# POWER.net
KiCad netlist of a schematic drawn in Altium Designer
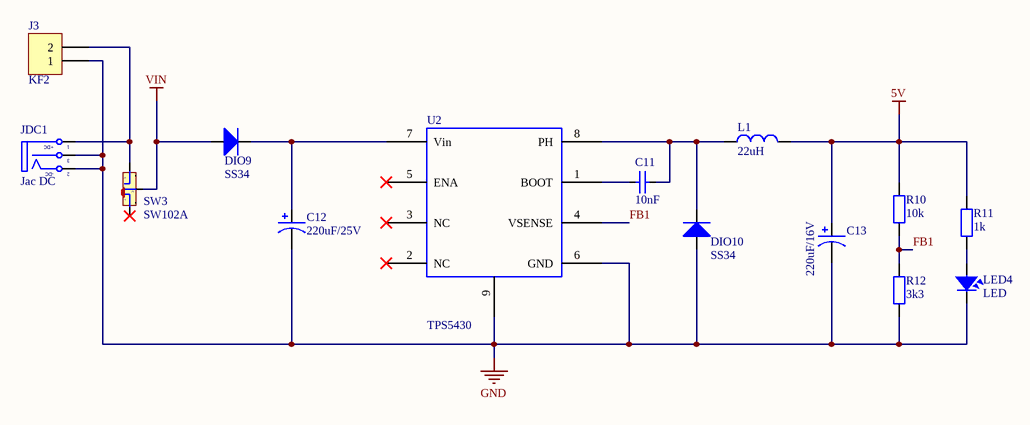
[diagram p0: POWER.SchDoc]

(export (version "E")
  (design (tool "Eeschema 10.0.6"))
  (components
    (comp (ref "C11")
      (value "10nF")
      (footprint "CAP_0805")
      (description "Capacitor")
      (fields (field (name "PUBLISHER") "Altium Limited"))
      (libsource (lib "My Library") (part "CapSMD"))
    )
    (comp (ref "C12")
      (value "220uF/25V")
      (footprint "C8mm")
      (description "Polarized Capacitor (Axial)")
      (fields (field (name "PUBLISHER") "Altium Limited"))
      (libsource (lib "My Library") (part "Cap Pol"))
    )
    (comp (ref "C13")
      (value "220uF/16V")
      (footprint "C8mm")
      (description "Polarized Capacitor (Axial)")
      (fields (field (name "PUBLISHER") "Altium Limited"))
      (libsource (lib "My Library") (part "Cap Pol"))
    )
    (comp (ref "DIO9")
      (value "SS34")
      (footprint "DIO-214AC(SMA)")
      (description "Default Diode")
      (fields (field (name "PUBLISHER") "Altium Limited"))
      (libsource (lib "My Library") (part "Diode SMD"))
    )
    (comp (ref "DIO10")
      (value "SS34")
      (footprint "DIO-214AC(SMA)")
      (description "Default Diode")
      (fields (field (name "PUBLISHER") "Altium Limited"))
      (libsource (lib "My Library") (part "Diode SMD"))
    )
    (comp (ref "J3")
      (value "KF2")
      (footprint "KF2-5.08")
      (fields
        (field (name "MANUFACTURER") "Würth Elektronik eiSos GmbH")
        (field (name "PARTNO") "691103110002")
        (field (name "CREATED BY") "Karrer Zheng")
      )
      (libsource (lib "My Library") (part "KF2"))
    )
    (comp (ref "JDC1")
      (value "Jac DC")
      (footprint "DC-IN")
      (description "Jac DC input")
      (libsource (lib "My Library") (part "DCIN"))
    )
    (comp (ref "L1")
      (value "22uH")
      (footprint "L-SMD-M-7.3x4.5")
      (description "Inductor")
      (libsource (lib "My Library") (part "Inductor"))
    )
    (comp (ref "LED4")
      (value "LED")
      (footprint "LED-0805-Red")
      (description "LED Single colour Green and Red")
      (libsource (lib "My Library") (part "LED"))
    )
    (comp (ref "R10")
      (value "10k")
      (footprint "RES-SMD-0805")
      (description "Resistor SMD")
      (fields
        (field (name "MANUFACTURER") "Generic Components")
        (field (name "PUBLISHER") "Altium Hobart Technology Centre")
      )
      (libsource (lib "My Library") (part "Resistor - SMD"))
    )
    (comp (ref "R11")
      (value "1k")
      (footprint "RES-SMD-0805")
      (description "Resistor SMD")
      (fields
        (field (name "MANUFACTURER") "Generic Components")
        (field (name "PUBLISHER") "Altium Hobart Technology Centre")
      )
      (libsource (lib "My Library") (part "Resistor - SMD"))
    )
    (comp (ref "R12")
      (value "3k3")
      (footprint "RES-SMD-0805")
      (description "Resistor SMD")
      (fields
        (field (name "MANUFACTURER") "Generic Components")
        (field (name "PUBLISHER") "Altium Hobart Technology Centre")
      )
      (libsource (lib "My Library") (part "Resistor - SMD"))
    )
    (comp (ref "SW3")
      (value "SW102A")
      (footprint "SW102")
      (description "Switch 102 on Broad")
      (libsource (lib "My Library") (part "SW102A"))
    )
    (comp (ref "U2")
      (value "TPS5430")
      (footprint "ESOP-8")
      (fields (field (name "NAME") "TPS5430"))
      (libsource (lib "My Library") (part "TPS5430"))
    )
  )
  (nets
    (net (code "1") (name "/FB1") (class "Default")
      (node (ref "R10") (pin "2") (pinfunction "2_2") (pintype "passive"))
      (node (ref "R12") (pin "1") (pinfunction "1_1") (pintype "passive"))
      (node (ref "U2") (pin "4") (pinfunction "VSENSE_4") (pintype "passive"))
    )
    (net (code "2") (name "5V") (class "Default")
      (node (ref "C13") (pin "1") (pinfunction "1_1") (pintype "passive"))
      (node (ref "L1") (pin "2") (pinfunction "2_2") (pintype "passive"))
      (node (ref "R10") (pin "1") (pinfunction "1_1") (pintype "passive"))
      (node (ref "R11") (pin "1") (pinfunction "1_1") (pintype "passive"))
    )
    (net (code "3") (name "GND") (class "Default")
      (node (ref "C12") (pin "2") (pinfunction "2_2") (pintype "passive"))
      (node (ref "C13") (pin "2") (pinfunction "2_2") (pintype "passive"))
      (node (ref "DIO10") (pin "1") (pinfunction "A_1") (pintype "passive"))
      (node (ref "J3") (pin "1") (pinfunction "1_1") (pintype "passive"))
      (node (ref "JDC1") (pin "2") (pinfunction "TN_2") (pintype "passive"))
      (node (ref "JDC1") (pin "3") (pinfunction "S_3") (pintype "power_in"))
      (node (ref "LED4") (pin "2") (pinfunction "2_2") (pintype "passive"))
      (node (ref "R12") (pin "2") (pinfunction "2_2") (pintype "passive"))
      (node (ref "U2") (pin "6") (pinfunction "GND_6") (pintype "passive"))
      (node (ref "U2") (pin "9") (pinfunction "PWR_PAD_9") (pintype "passive"))
    )
    (net (code "4") (name "Net-(DIO9-K)") (class "Default")
      (node (ref "C12") (pin "1") (pinfunction "1_1") (pintype "passive"))
      (node (ref "DIO9") (pin "2") (pinfunction "K_2") (pintype "passive"))
      (node (ref "U2") (pin "7") (pinfunction "Vin_7") (pintype "passive"))
    )
    (net (code "5") (name "Net-(DIO10-K)") (class "Default")
      (node (ref "C11") (pin "2") (pinfunction "2_2") (pintype "passive"))
      (node (ref "DIO10") (pin "2") (pinfunction "K_2") (pintype "passive"))
      (node (ref "L1") (pin "1") (pinfunction "1_1") (pintype "passive"))
      (node (ref "U2") (pin "8") (pinfunction "PH_8") (pintype "passive"))
    )
    (net (code "6") (name "Net-(JDC1-T)") (class "Default")
      (node (ref "J3") (pin "2") (pinfunction "2_2") (pintype "passive"))
      (node (ref "JDC1") (pin "1") (pinfunction "T_1") (pintype "passive"))
      (node (ref "SW3") (pin "3") (pinfunction "3_3") (pintype "passive"))
    )
    (net (code "7") (name "Net-(LED4-Pad1)") (class "Default")
      (node (ref "LED4") (pin "1") (pinfunction "1_1") (pintype "passive"))
      (node (ref "R11") (pin "2") (pinfunction "2_2") (pintype "passive"))
    )
    (net (code "8") (name "Net-(U2-BOOT)") (class "Default")
      (node (ref "C11") (pin "1") (pinfunction "1_1") (pintype "passive"))
      (node (ref "U2") (pin "1") (pinfunction "BOOT_1") (pintype "passive"))
    )
    (net (code "9") (name "VIN") (class "Default")
      (node (ref "DIO9") (pin "1") (pinfunction "A_1") (pintype "passive"))
      (node (ref "SW3") (pin "2") (pinfunction "2_2") (pintype "passive"))
    )
    (net (code "10") (name "unconnected-(SW3-Pad1)") (class "Default")
      (node (ref "SW3") (pin "1") (pinfunction "1_1") (pintype "passive+no_connect"))
    )
    (net (code "11") (name "unconnected-(SW3-Pad4)") (class "Default")
      (node (ref "SW3") (pin "4") (pinfunction "4_4") (pintype "passive"))
    )
    (net (code "12") (name "unconnected-(SW3-Pad5)") (class "Default")
      (node (ref "SW3") (pin "5") (pinfunction "5_5") (pintype "passive"))
    )
    (net (code "13") (name "unconnected-(U2-ENA-Pad5)") (class "Default")
      (node (ref "U2") (pin "5") (pinfunction "ENA_5") (pintype "passive+no_connect"))
    )
    (net (code "14") (name "unconnected-(U2-NC-Pad2)") (class "Default")
      (node (ref "U2") (pin "2") (pinfunction "NC_2") (pintype "passive+no_connect"))
    )
    (net (code "15") (name "unconnected-(U2-NC-Pad3)") (class "Default")
      (node (ref "U2") (pin "3") (pinfunction "NC_3") (pintype "passive+no_connect"))
    )
  )
)
